# ESP32.net
KiCad netlist of a schematic drawn in Altium Designer
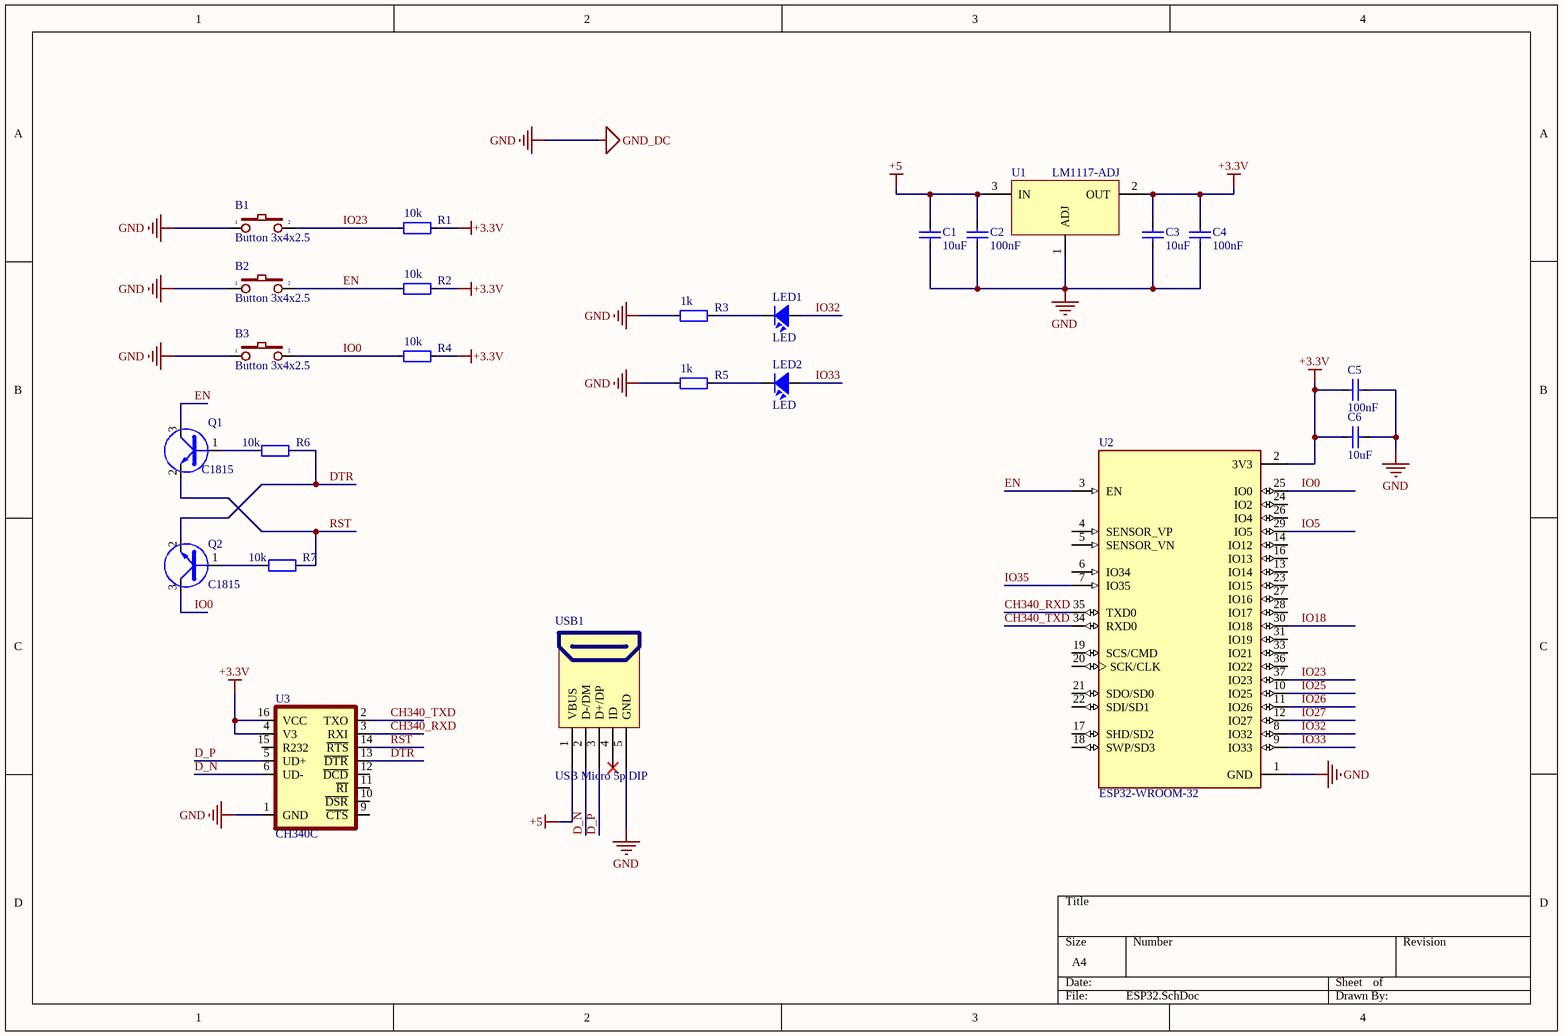
[diagram p0: ESP32.SchDoc]

(export (version "E")
  (design (tool "Eeschema 10.0.6"))
  (components
    (comp (ref "B1")
      (value "Button 3x4x2.5")
      (footprint "Button 3x4x2.5")
      (libsource (lib "My Library") (part "Button 3x4x2.5"))
    )
    (comp (ref "B2")
      (value "Button 3x4x2.5")
      (footprint "Button 3x4x2.5")
      (libsource (lib "My Library") (part "Button 3x4x2.5"))
    )
    (comp (ref "B3")
      (value "Button 3x4x2.5")
      (footprint "Button 3x4x2.5")
      (libsource (lib "My Library") (part "Button 3x4x2.5"))
    )
    (comp (ref "C1")
      (value "10uF")
      (footprint "CAP_0805")
      (description "Capacitor")
      (fields (field (name "PUBLISHER") "Altium Limited"))
      (libsource (lib "My Library") (part "CapSMD"))
    )
    (comp (ref "C2")
      (value "100nF")
      (footprint "CAP_0805")
      (description "Capacitor")
      (fields (field (name "PUBLISHER") "Altium Limited"))
      (libsource (lib "My Library") (part "CapSMD"))
    )
    (comp (ref "C3")
      (value "10uF")
      (footprint "CAP_0805")
      (description "Capacitor")
      (fields (field (name "PUBLISHER") "Altium Limited"))
      (libsource (lib "My Library") (part "CapSMD"))
    )
    (comp (ref "C4")
      (value "100nF")
      (footprint "CAP_0805")
      (description "Capacitor")
      (fields (field (name "PUBLISHER") "Altium Limited"))
      (libsource (lib "My Library") (part "CapSMD"))
    )
    (comp (ref "C5")
      (value "100nF")
      (footprint "CAP_0805")
      (description "Capacitor")
      (fields (field (name "PUBLISHER") "Altium Limited"))
      (libsource (lib "My Library") (part "CapSMD"))
    )
    (comp (ref "C6")
      (value "10uF")
      (footprint "CAP_0805")
      (description "Capacitor")
      (fields (field (name "PUBLISHER") "Altium Limited"))
      (libsource (lib "My Library") (part "CapSMD"))
    )
    (comp (ref "LED1")
      (value "LED")
      (footprint "LED-0805-Red")
      (description "LED Single colour Green and Red")
      (libsource (lib "My Library") (part "LED"))
    )
    (comp (ref "LED2")
      (value "LED")
      (footprint "LED-0805-Red")
      (description "LED Single colour Green and Red")
      (libsource (lib "My Library") (part "LED"))
    )
    (comp (ref "Q1")
      (value "C1815")
      (footprint "SOT23D")
      (description "NPN 600mW, ECB")
      (libsource (lib "My Library") (part "2SC1815"))
    )
    (comp (ref "Q2")
      (value "C1815")
      (footprint "SOT23D")
      (description "NPN 600mW, ECB")
      (libsource (lib "") (part "2SC1815_1"))
    )
    (comp (ref "R1")
      (value "10k")
      (footprint "RES-SMD-0805")
      (description "Resistor")
      (fields
        (field (name "MANUFACTURER") "Generic Components")
        (field (name "PUBLISHER") "Altium Hobart Technology Centre")
      )
      (libsource (lib "My Library") (part "Resistor - SMD"))
    )
    (comp (ref "R2")
      (value "10k")
      (footprint "RES-SMD-0805")
      (description "Resistor")
      (fields
        (field (name "MANUFACTURER") "Generic Components")
        (field (name "PUBLISHER") "Altium Hobart Technology Centre")
      )
      (libsource (lib "My Library") (part "Resistor - SMD"))
    )
    (comp (ref "R3")
      (value "1k")
      (footprint "RES-SMD-0805")
      (description "Resistor")
      (fields
        (field (name "MANUFACTURER") "Generic Components")
        (field (name "PUBLISHER") "Altium Hobart Technology Centre")
      )
      (libsource (lib "My Library") (part "Resistor - SMD"))
    )
    (comp (ref "R4")
      (value "10k")
      (footprint "RES-SMD-0805")
      (description "Resistor")
      (fields
        (field (name "MANUFACTURER") "Generic Components")
        (field (name "PUBLISHER") "Altium Hobart Technology Centre")
      )
      (libsource (lib "My Library") (part "Resistor - SMD"))
    )
    (comp (ref "R5")
      (value "1k")
      (footprint "RES-SMD-0805")
      (description "Resistor")
      (fields
        (field (name "MANUFACTURER") "Generic Components")
        (field (name "PUBLISHER") "Altium Hobart Technology Centre")
      )
      (libsource (lib "My Library") (part "Resistor - SMD"))
    )
    (comp (ref "R6")
      (value "10k")
      (footprint "RES-SMD-0805")
      (description "Resistor")
      (fields
        (field (name "MANUFACTURER") "Generic Components")
        (field (name "PUBLISHER") "Altium Hobart Technology Centre")
      )
      (libsource (lib "My Library") (part "Resistor - SMD"))
    )
    (comp (ref "R7")
      (value "10k")
      (footprint "RES-SMD-0805")
      (description "Resistor")
      (fields
        (field (name "MANUFACTURER") "Generic Components")
        (field (name "PUBLISHER") "Altium Hobart Technology Centre")
      )
      (libsource (lib "My Library") (part "Resistor - SMD"))
    )
    (comp (ref "U1")
      (value "LM1117-ADJ")
      (footprint "LM1117-SOP")
      (description "800mA Low-Dropout Linear Regulator")
      (fields (field (name "CREATOR") "Nguyen Ba Bien"))
      (libsource (lib "My Library") (part "LM1117-ADJ"))
    )
    (comp (ref "U2")
      (value "ESP32-WROOM-32")
      (footprint "MODULE_ESP32-WROOM-32")
      (description "Bluetooth, WiFi Transceiver Module 2.4GHz ~ 2.5GHz Surface Mount")
      (fields (field (name "MF") "Espressif Systems") (field (name "DIGI-KEY_PART_NUMBER") "1904-1010-1-ND"))
      (libsource (lib "My Library") (part "ESP32-WROOM-32"))
    )
    (comp (ref "U3")
      (value "CH340C")
      (footprint "SO016")
      (description "USB to serial chip CH340")
      (fields (field (name "MF") "WCH"))
      (libsource (lib "My Library") (part "CH340C"))
    )
    (comp (ref "USB1")
      (value "USB Micro 5p DIP")
      (footprint "USB Micro 5p DIP")
      (description "USB Type B")
      (libsource (lib "Altium_Lib_by_KhueNguyenCreator") (part "USB Micro 5p DIP"))
    )
  )
  (nets
    (net (code "1") (name "+3.3V") (class "Default")
      (node (ref "C3") (pin "1") (pinfunction "1_1") (pintype "passive"))
      (node (ref "C4") (pin "1") (pinfunction "1_1") (pintype "passive"))
      (node (ref "C5") (pin "1") (pinfunction "1_1") (pintype "passive"))
      (node (ref "C6") (pin "1") (pinfunction "1_1") (pintype "passive"))
      (node (ref "R1") (pin "1") (pinfunction "1_1") (pintype "passive"))
      (node (ref "R2") (pin "1") (pinfunction "1_1") (pintype "passive"))
      (node (ref "R4") (pin "1") (pinfunction "1_1") (pintype "passive"))
      (node (ref "U1") (pin "2") (pinfunction "OUT_2") (pintype "passive"))
      (node (ref "U2") (pin "2") (pinfunction "3V3_2") (pintype "power_in"))
      (node (ref "U3") (pin "16") (pinfunction "VCC_16") (pintype "bidirectional"))
      (node (ref "U3") (pin "4") (pinfunction "V3_4") (pintype "bidirectional"))
    )
    (net (code "2") (name "+5") (class "Default")
      (node (ref "C1") (pin "1") (pinfunction "1_1") (pintype "passive"))
      (node (ref "C2") (pin "1") (pinfunction "1_1") (pintype "passive"))
      (node (ref "U1") (pin "3") (pinfunction "IN_3") (pintype "passive"))
      (node (ref "USB1") (pin "1") (pinfunction "VBUS_1") (pintype "passive"))
    )
    (net (code "3") (name "/CH340_RXD") (class "Default")
      (node (ref "U2") (pin "35") (pinfunction "TXD0_35") (pintype "bidirectional"))
      (node (ref "U3") (pin "3") (pinfunction "RXI_3") (pintype "bidirectional"))
    )
    (net (code "4") (name "/CH340_TXD") (class "Default")
      (node (ref "U2") (pin "34") (pinfunction "RXD0_34") (pintype "bidirectional"))
      (node (ref "U3") (pin "2") (pinfunction "TXO_2") (pintype "bidirectional"))
    )
    (net (code "5") (name "/DTR") (class "Default")
      (node (ref "Q2") (pin "2") (pinfunction "E_2") (pintype "passive"))
      (node (ref "R6") (pin "1") (pinfunction "1_1") (pintype "passive"))
      (node (ref "U3") (pin "13") (pinfunction "~{DTR}_13") (pintype "bidirectional"))
    )
    (net (code "6") (name "/D_N") (class "Default")
      (node (ref "U3") (pin "6") (pinfunction "UD-_6") (pintype "bidirectional"))
      (node (ref "USB1") (pin "2") (pinfunction "D-/DM_2") (pintype "passive"))
    )
    (net (code "7") (name "/D_P") (class "Default")
      (node (ref "U3") (pin "5") (pinfunction "UD+_5") (pintype "bidirectional"))
      (node (ref "USB1") (pin "3") (pinfunction "D+/DP_3") (pintype "passive"))
    )
    (net (code "8") (name "/EN") (class "Default")
      (node (ref "B2") (pin "2") (pinfunction "2_2") (pintype "passive"))
      (node (ref "Q1") (pin "3") (pinfunction "C_3") (pintype "passive"))
      (node (ref "R2") (pin "2") (pinfunction "2_2") (pintype "passive"))
      (node (ref "U2") (pin "3") (pinfunction "EN_3") (pintype "input"))
    )
    (net (code "9") (name "/IO0") (class "Default")
      (node (ref "B3") (pin "2") (pinfunction "2_2") (pintype "passive"))
      (node (ref "Q2") (pin "3") (pinfunction "C_3") (pintype "passive"))
      (node (ref "R4") (pin "2") (pinfunction "2_2") (pintype "passive"))
      (node (ref "U2") (pin "25") (pinfunction "IO0_25") (pintype "bidirectional"))
    )
    (net (code "10") (name "/IO5") (class "Default")
      (node (ref "U2") (pin "29") (pinfunction "IO5_29") (pintype "bidirectional"))
    )
    (net (code "11") (name "/IO18") (class "Default")
      (node (ref "U2") (pin "30") (pinfunction "IO18_30") (pintype "bidirectional"))
    )
    (net (code "12") (name "/IO23") (class "Default")
      (node (ref "B1") (pin "2") (pinfunction "2_2") (pintype "passive"))
      (node (ref "R1") (pin "2") (pinfunction "2_2") (pintype "passive"))
      (node (ref "U2") (pin "37") (pinfunction "IO23_37") (pintype "bidirectional"))
    )
    (net (code "13") (name "/IO25") (class "Default")
      (node (ref "U2") (pin "10") (pinfunction "IO25_10") (pintype "bidirectional"))
    )
    (net (code "14") (name "/IO26") (class "Default")
      (node (ref "U2") (pin "11") (pinfunction "IO26_11") (pintype "bidirectional"))
    )
    (net (code "15") (name "/IO27") (class "Default")
      (node (ref "U2") (pin "12") (pinfunction "IO27_12") (pintype "bidirectional"))
    )
    (net (code "16") (name "/IO32") (class "Default")
      (node (ref "LED1") (pin "1") (pinfunction "1_1") (pintype "passive"))
      (node (ref "U2") (pin "8") (pinfunction "IO32_8") (pintype "bidirectional"))
    )
    (net (code "17") (name "/IO33") (class "Default")
      (node (ref "LED2") (pin "1") (pinfunction "1_1") (pintype "passive"))
      (node (ref "U2") (pin "9") (pinfunction "IO33_9") (pintype "bidirectional"))
    )
    (net (code "18") (name "/IO35") (class "Default")
      (node (ref "U2") (pin "7") (pinfunction "IO35_7") (pintype "input"))
    )
    (net (code "19") (name "/RST") (class "Default")
      (node (ref "Q1") (pin "2") (pinfunction "E_2") (pintype "passive"))
      (node (ref "R7") (pin "1") (pinfunction "1_1") (pintype "passive"))
      (node (ref "U3") (pin "14") (pinfunction "~{RTS}_14") (pintype "bidirectional"))
    )
    (net (code "20") (name "GND") (class "Default")
      (node (ref "B1") (pin "1") (pinfunction "1_1") (pintype "passive"))
      (node (ref "B2") (pin "1") (pinfunction "1_1") (pintype "passive"))
      (node (ref "B3") (pin "1") (pinfunction "1_1") (pintype "passive"))
      (node (ref "C1") (pin "2") (pinfunction "2_2") (pintype "passive"))
      (node (ref "C2") (pin "2") (pinfunction "2_2") (pintype "passive"))
      (node (ref "C3") (pin "2") (pinfunction "2_2") (pintype "passive"))
      (node (ref "C4") (pin "2") (pinfunction "2_2") (pintype "passive"))
      (node (ref "C5") (pin "2") (pinfunction "2_2") (pintype "passive"))
      (node (ref "C6") (pin "2") (pinfunction "2_2") (pintype "passive"))
      (node (ref "R3") (pin "2") (pinfunction "2_2") (pintype "passive"))
      (node (ref "R5") (pin "2") (pinfunction "2_2") (pintype "passive"))
      (node (ref "U1") (pin "1") (pinfunction "ADJ_1") (pintype "passive"))
      (node (ref "U2") (pin "1") (pinfunction "GND_1") (pintype "power_in"))
      (node (ref "U3") (pin "1") (pinfunction "GND_1") (pintype "bidirectional"))
      (node (ref "USB1") (pin "5") (pinfunction "GND_5") (pintype "passive"))
    )
    (net (code "21") (name "Net-(LED1-Pad2)") (class "Default")
      (node (ref "LED1") (pin "2") (pinfunction "2_2") (pintype "passive"))
      (node (ref "R3") (pin "1") (pinfunction "1_1") (pintype "passive"))
    )
    (net (code "22") (name "Net-(LED2-Pad2)") (class "Default")
      (node (ref "LED2") (pin "2") (pinfunction "2_2") (pintype "passive"))
      (node (ref "R5") (pin "1") (pinfunction "1_1") (pintype "passive"))
    )
    (net (code "23") (name "Net-(Q1-B)") (class "Default")
      (node (ref "Q1") (pin "1") (pinfunction "B_1") (pintype "passive"))
      (node (ref "R6") (pin "2") (pinfunction "2_2") (pintype "passive"))
    )
    (net (code "24") (name "Net-(Q2-B)") (class "Default")
      (node (ref "Q2") (pin "1") (pinfunction "B_1") (pintype "passive"))
      (node (ref "R7") (pin "2") (pinfunction "2_2") (pintype "passive"))
    )
    (net (code "25") (name "unconnected-(U2-IO2-Pad24)") (class "Default")
      (node (ref "U2") (pin "24") (pinfunction "IO2_24") (pintype "bidirectional"))
    )
    (net (code "26") (name "unconnected-(U2-IO4-Pad26)") (class "Default")
      (node (ref "U2") (pin "26") (pinfunction "IO4_26") (pintype "bidirectional"))
    )
    (net (code "27") (name "unconnected-(U2-IO12-Pad14)") (class "Default")
      (node (ref "U2") (pin "14") (pinfunction "IO12_14") (pintype "bidirectional"))
    )
    (net (code "28") (name "unconnected-(U2-IO13-Pad16)") (class "Default")
      (node (ref "U2") (pin "16") (pinfunction "IO13_16") (pintype "bidirectional"))
    )
    (net (code "29") (name "unconnected-(U2-IO14-Pad13)") (class "Default")
      (node (ref "U2") (pin "13") (pinfunction "IO14_13") (pintype "bidirectional"))
    )
    (net (code "30") (name "unconnected-(U2-IO15-Pad23)") (class "Default")
      (node (ref "U2") (pin "23") (pinfunction "IO15_23") (pintype "bidirectional"))
    )
    (net (code "31") (name "unconnected-(U2-IO16-Pad27)") (class "Default")
      (node (ref "U2") (pin "27") (pinfunction "IO16_27") (pintype "bidirectional"))
    )
    (net (code "32") (name "unconnected-(U2-IO17-Pad28)") (class "Default")
      (node (ref "U2") (pin "28") (pinfunction "IO17_28") (pintype "bidirectional"))
    )
    (net (code "33") (name "unconnected-(U2-IO19-Pad31)") (class "Default")
      (node (ref "U2") (pin "31") (pinfunction "IO19_31") (pintype "bidirectional"))
    )
    (net (code "34") (name "unconnected-(U2-IO21-Pad33)") (class "Default")
      (node (ref "U2") (pin "33") (pinfunction "IO21_33") (pintype "bidirectional"))
    )
    (net (code "35") (name "unconnected-(U2-IO22-Pad36)") (class "Default")
      (node (ref "U2") (pin "36") (pinfunction "IO22_36") (pintype "bidirectional"))
    )
    (net (code "36") (name "unconnected-(U2-IO34-Pad6)") (class "Default")
      (node (ref "U2") (pin "6") (pinfunction "IO34_6") (pintype "input"))
    )
    (net (code "37") (name "unconnected-(U2-SCK{slash}CLK-Pad20)") (class "Default")
      (node (ref "U2") (pin "20") (pinfunction "SCK/CLK_20") (pintype "bidirectional"))
    )
    (net (code "38") (name "unconnected-(U2-SCS{slash}CMD-Pad19)") (class "Default")
      (node (ref "U2") (pin "19") (pinfunction "SCS/CMD_19") (pintype "bidirectional"))
    )
    (net (code "39") (name "unconnected-(U2-SDI{slash}SD1-Pad22)") (class "Default")
      (node (ref "U2") (pin "22") (pinfunction "SDI/SD1_22") (pintype "bidirectional"))
    )
    (net (code "40") (name "unconnected-(U2-SDO{slash}SD0-Pad21)") (class "Default")
      (node (ref "U2") (pin "21") (pinfunction "SDO/SD0_21") (pintype "bidirectional"))
    )
    (net (code "41") (name "unconnected-(U2-SENSOR_VN-Pad5)") (class "Default")
      (node (ref "U2") (pin "5") (pinfunction "SENSOR_VN_5") (pintype "input"))
    )
    (net (code "42") (name "unconnected-(U2-SENSOR_VP-Pad4)") (class "Default")
      (node (ref "U2") (pin "4") (pinfunction "SENSOR_VP_4") (pintype "input"))
    )
    (net (code "43") (name "unconnected-(U2-SHD{slash}SD2-Pad17)") (class "Default")
      (node (ref "U2") (pin "17") (pinfunction "SHD/SD2_17") (pintype "bidirectional"))
    )
    (net (code "44") (name "unconnected-(U2-SWP{slash}SD3-Pad18)") (class "Default")
      (node (ref "U2") (pin "18") (pinfunction "SWP/SD3_18") (pintype "bidirectional"))
    )
    (net (code "45") (name "unconnected-(U3-R232-Pad15)") (class "Default")
      (node (ref "U3") (pin "15") (pinfunction "R232_15") (pintype "bidirectional"))
    )
    (net (code "46") (name "unconnected-(U3-~{CTS}-Pad9)") (class "Default")
      (node (ref "U3") (pin "9") (pinfunction "~{CTS}_9") (pintype "bidirectional"))
    )
    (net (code "47") (name "unconnected-(U3-~{DCD}-Pad12)") (class "Default")
      (node (ref "U3") (pin "12") (pinfunction "~{DCD}_12") (pintype "bidirectional"))
    )
    (net (code "48") (name "unconnected-(U3-~{DSR}-Pad10)") (class "Default")
      (node (ref "U3") (pin "10") (pinfunction "~{DSR}_10") (pintype "bidirectional"))
    )
    (net (code "49") (name "unconnected-(U3-~{RI}-Pad11)") (class "Default")
      (node (ref "U3") (pin "11") (pinfunction "~{RI}_11") (pintype "bidirectional"))
    )
    (net (code "50") (name "unconnected-(USB1-ID-Pad4)") (class "Default")
      (node (ref "USB1") (pin "4") (pinfunction "ID_4") (pintype "passive+no_connect"))
    )
  )
)
